# V2_rampGen.net
KiCad netlist of a schematic drawn in Altium Designer
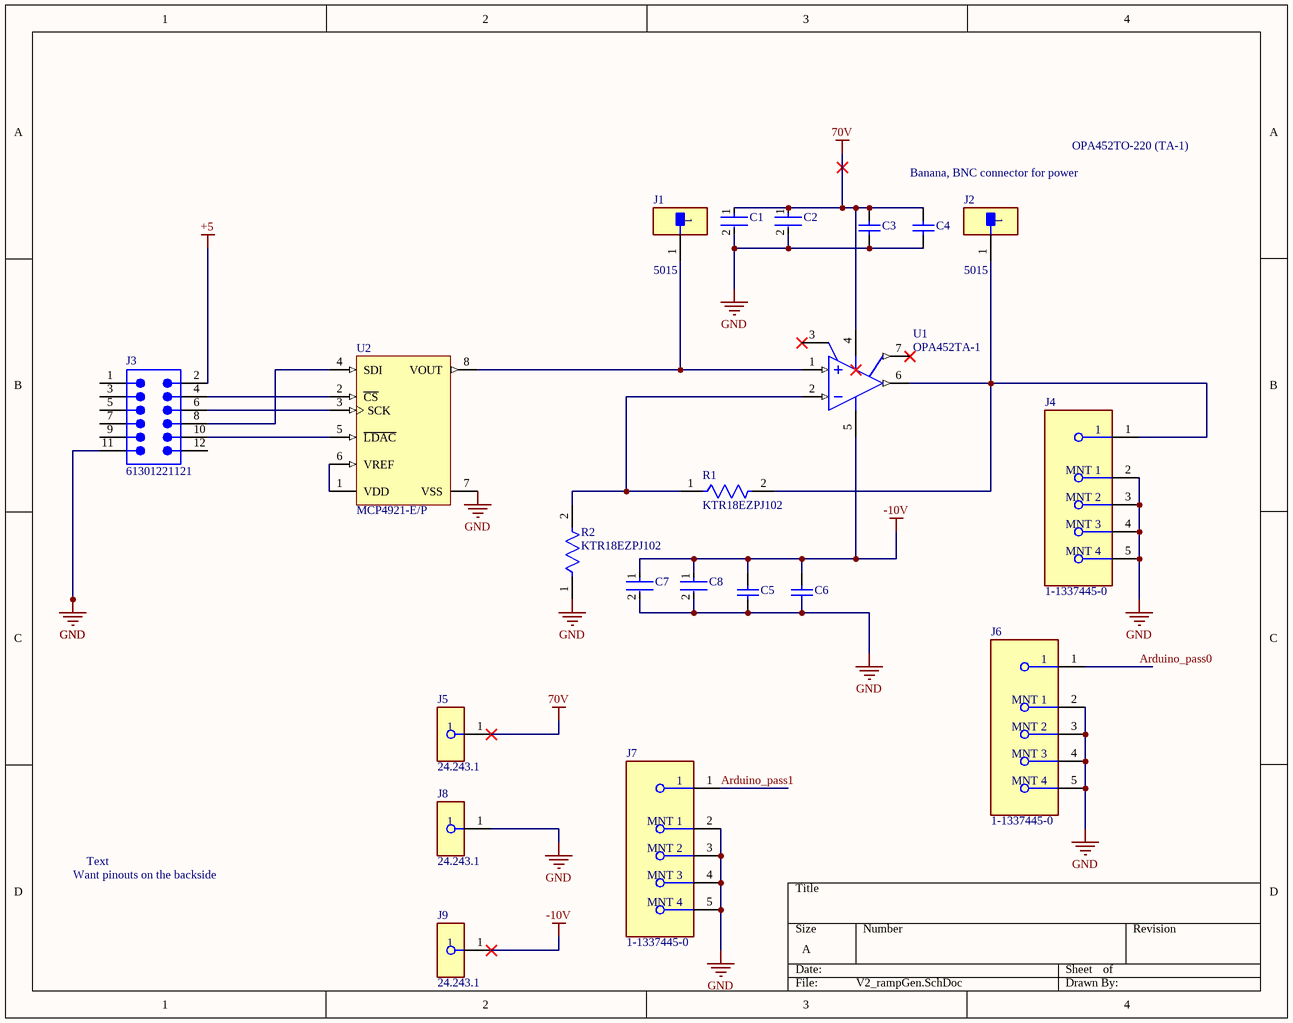
[diagram p0: V2_rampGen.SchDoc]

(export (version "E")
  (design (tool "Eeschema 10.0.6"))
  (components
    (comp (ref "C1")
      (value "C3216JB1A106M160AA")
      (footprint "FP-C3216-160-0_2-IPC_C")
      (description "Multilayer Ceramic Capacitors 10uF ±20% 10V JB SMD 1206")
      (fields (field (name "TOLERANCE") "20%"))
      (libsource (lib "Altium Content Vault") (part "11868f565c42a9108669ba33697ecf6"))
    )
    (comp (ref "C2")
      (value "C3216JB1A106M160AA")
      (footprint "FP-C3216-160-0_2-IPC_C")
      (description "Multilayer Ceramic Capacitors 10uF ±20% 10V JB SMD 1206")
      (fields (field (name "TOLERANCE") "20%"))
      (libsource (lib "Altium Content Vault") (part "11868f565c42a9108669ba33697ecf6"))
    )
    (comp (ref "C3")
      (value "CAP 100pF 100V 1206(3216)")
      (footprint "CAPC1206(3216)100_N")
      (description "CAP 100pF 100V ±1% 1206 (3216 Metric) Thickness 1mm SMD")
      (fields (field (name "TOLERANCE") "Â±1%"))
      (libsource (lib "Altium Content Vault") (part "CAP"))
    )
    (comp (ref "C4")
      (value "CAP 100pF 100V 1206(3216)")
      (footprint "CAPC1206(3216)100_N")
      (description "CAP 100pF 100V ±1% 1206 (3216 Metric) Thickness 1mm SMD")
      (fields (field (name "TOLERANCE") "Â±1%"))
      (libsource (lib "Altium Content Vault") (part "CAP"))
    )
    (comp (ref "C5")
      (value "CAP 100pF 100V 1206(3216)")
      (footprint "CAPC1206(3216)100_N")
      (description "CAP 100pF 100V ±1% 1206 (3216 Metric) Thickness 1mm SMD")
      (fields (field (name "TOLERANCE") "Â±1%"))
      (libsource (lib "Altium Content Vault") (part "CAP"))
    )
    (comp (ref "C6")
      (value "CAP 100pF 100V 1206(3216)")
      (footprint "CAPC1206(3216)100_N")
      (description "CAP 100pF 100V ±1% 1206 (3216 Metric) Thickness 1mm SMD")
      (fields (field (name "TOLERANCE") "Â±1%"))
      (libsource (lib "Altium Content Vault") (part "CAP"))
    )
    (comp (ref "C7")
      (value "C3216JB1A106M160AA")
      (footprint "FP-C3216-160-0_2-IPC_C")
      (description "Multilayer Ceramic Capacitors 10uF ±20% 10V JB SMD 1206")
      (fields (field (name "TOLERANCE") "20%"))
      (libsource (lib "Altium Content Vault") (part "11868f565c42a9108669ba33697ecf6"))
    )
    (comp (ref "C8")
      (value "C3216JB1A106M160AA")
      (footprint "FP-C3216-160-0_2-IPC_C")
      (description "Multilayer Ceramic Capacitors 10uF ±20% 10V JB SMD 1206")
      (fields (field (name "TOLERANCE") "20%"))
      (libsource (lib "Altium Content Vault") (part "11868f565c42a9108669ba33697ecf6"))
    )
    (comp (ref "J1")
      (value "5015")
      (footprint "FP-5015-MFG")
      (description "PC TEST POINT MINIATURE")
      (fields
        (field (name "MANUFACTURER") "keystone")
        (field (name "OCTOPART") "https://octopart.com/5015-keystone-3822")
      )
      (libsource (lib "Altium Content Vault") (part "dd45045ce8184df9e99e12baf3f412c"))
    )
    (comp (ref "J2")
      (value "5015")
      (footprint "FP-5015-MFG")
      (description "PC TEST POINT MINIATURE")
      (fields
        (field (name "MANUFACTURER") "keystone")
        (field (name "OCTOPART") "https://octopart.com/5015-keystone-3822")
      )
      (libsource (lib "Altium Content Vault") (part "dd45045ce8184df9e99e12baf3f412c"))
    )
    (comp (ref "J3")
      (value "61301221121")
      (footprint "61301221121")
      (libsource (lib "Altium Content Vault") (part "Header_Male_2R_12P"))
    )
    (comp (ref "J4")
      (value "1-1337445-0")
      (footprint "FP-1-1337445-0-MFG")
      (description "CONN BNC JACK STR 50 OHM PCB")
      (libsource (lib "Altium Content Vault") (part "c65b8a639cdaef1819ea20b5466f8fa"))
    )
    (comp (ref "J5")
      (value "24.243.1")
      (footprint "FP-24_243_1-MFG")
      (description "Banana Test Connector, 4mm, Socket, PCB Mount, 24 A, 60 VDC, Silver Plated Contacts, Green")
      (libsource (lib "Altium Content Vault") (part "98815daf2f2c152b0c43f5ab9800df6"))
    )
    (comp (ref "J6")
      (value "1-1337445-0")
      (footprint "FP-1-1337445-0-MFG")
      (description "CONN BNC JACK STR 50 OHM PCB")
      (libsource (lib "Altium Content Vault") (part "c65b8a639cdaef1819ea20b5466f8fa"))
    )
    (comp (ref "J7")
      (value "1-1337445-0")
      (footprint "FP-1-1337445-0-MFG")
      (description "CONN BNC JACK STR 50 OHM PCB")
      (libsource (lib "Altium Content Vault") (part "c65b8a639cdaef1819ea20b5466f8fa"))
    )
    (comp (ref "J8")
      (value "24.243.1")
      (footprint "FP-24_243_1-MFG")
      (description "Banana Test Connector, 4mm, Socket, PCB Mount, 24 A, 60 VDC, Silver Plated Contacts, Green")
      (libsource (lib "Altium Content Vault") (part "98815daf2f2c152b0c43f5ab9800df6"))
    )
    (comp (ref "J9")
      (value "24.243.1")
      (footprint "FP-24_243_1-MFG")
      (description "Banana Test Connector, 4mm, Socket, PCB Mount, 24 A, 60 VDC, Silver Plated Contacts, Green")
      (libsource (lib "Altium Content Vault") (part "98815daf2f2c152b0c43f5ab9800df6"))
    )
    (comp (ref "R1")
      (value "KTR18EZPJ102")
      (footprint "FP-KTR18-IPC_A")
      (description "Res Thick Film 1206 1kΩ 5% 0.1W ±200ppm/°C Automotive Paper T/R")
      (fields (field (name "TOLERANCE") "5%"))
      (libsource (lib "Altium Content Vault") (part "1029c3af85768c4190bb7ad29bc67b5"))
    )
    (comp (ref "R2")
      (value "KTR18EZPJ102")
      (footprint "FP-KTR18-IPC_A")
      (description "Res Thick Film 1206 1kΩ 5% 0.1W ±200ppm/°C Automotive Paper T/R")
      (fields (field (name "TOLERANCE") "5%"))
      (libsource (lib "Altium Content Vault") (part "1029c3af85768c4190bb7ad29bc67b5"))
    )
    (comp (ref "U1")
      (value "OPA452TA-1")
      (footprint "KVT0007A")
      (description "Operational Amplifier, 20 to 80 V, -40 to 125 degC, 7-pin FM (KVT7), Green (RoHS & no Sb/Br)")
      (fields (field (name "MANUFACTURER") "Texas Instruments"))
      (libsource (lib "Altium Content Vault") (part "TI-OPA452_453-7"))
    )
    (comp (ref "U2")
      (value "MCP4921-E/P")
      (footprint "PDIP300-P8")
      (description "12-Bit DAC with SPI Interface, 8-Pin PDIP, Extended Temperature")
      (libsource (lib "Altium Content Vault") (part "CON-DAC-MCP4921-8"))
    )
  )
  (nets
    (net (code "1") (name "+5") (class "Default")
      (node (ref "J3") (pin "2") (pinfunction "2_2") (pintype "passive"))
    )
    (net (code "2") (name "-10V") (class "Default")
      (node (ref "C5") (pin "2") (pinfunction "2_2") (pintype "passive"))
      (node (ref "C6") (pin "2") (pinfunction "2_2") (pintype "passive"))
      (node (ref "C7") (pin "1") (pinfunction "1_1") (pintype "passive"))
      (node (ref "C8") (pin "1") (pinfunction "1_1") (pintype "passive"))
      (node (ref "J9") (pin "1") (pinfunction "1_1") (pintype "passive"))
      (node (ref "U1") (pin "5") (pinfunction "V+_5") (pintype "power_in"))
    )
    (net (code "3") (name "/Arduino_pass0") (class "Default")
      (node (ref "J6") (pin "1") (pinfunction "1_1") (pintype "passive"))
    )
    (net (code "4") (name "/Arduino_pass1") (class "Default")
      (node (ref "J7") (pin "1") (pinfunction "1_1") (pintype "passive"))
    )
    (net (code "5") (name "70V") (class "Default")
      (node (ref "C1") (pin "1") (pinfunction "1_1") (pintype "passive"))
      (node (ref "C2") (pin "1") (pinfunction "1_1") (pintype "passive"))
      (node (ref "C3") (pin "2") (pinfunction "2_2") (pintype "passive"))
      (node (ref "C4") (pin "2") (pinfunction "2_2") (pintype "passive"))
      (node (ref "J5") (pin "1") (pinfunction "1_1") (pintype "passive"))
      (node (ref "U1") (pin "4") (pinfunction "V-_4") (pintype "power_in"))
    )
    (net (code "6") (name "GND") (class "Default")
      (node (ref "C1") (pin "2") (pinfunction "2_2") (pintype "passive"))
      (node (ref "C2") (pin "2") (pinfunction "2_2") (pintype "passive"))
      (node (ref "C3") (pin "1") (pinfunction "1_1") (pintype "passive"))
      (node (ref "C4") (pin "1") (pinfunction "1_1") (pintype "passive"))
      (node (ref "C5") (pin "1") (pinfunction "1_1") (pintype "passive"))
      (node (ref "C6") (pin "1") (pinfunction "1_1") (pintype "passive"))
      (node (ref "C7") (pin "2") (pinfunction "2_2") (pintype "passive"))
      (node (ref "C8") (pin "2") (pinfunction "2_2") (pintype "passive"))
      (node (ref "J3") (pin "11") (pinfunction "11_11") (pintype "passive"))
      (node (ref "J4") (pin "2") (pinfunction "MNT_1_2") (pintype "passive"))
      (node (ref "J4") (pin "3") (pinfunction "MNT_2_3") (pintype "passive"))
      (node (ref "J4") (pin "4") (pinfunction "MNT_3_4") (pintype "passive"))
      (node (ref "J4") (pin "5") (pinfunction "MNT_4_5") (pintype "passive"))
      (node (ref "J6") (pin "2") (pinfunction "MNT_1_2") (pintype "passive"))
      (node (ref "J6") (pin "3") (pinfunction "MNT_2_3") (pintype "passive"))
      (node (ref "J6") (pin "4") (pinfunction "MNT_3_4") (pintype "passive"))
      (node (ref "J6") (pin "5") (pinfunction "MNT_4_5") (pintype "passive"))
      (node (ref "J7") (pin "2") (pinfunction "MNT_1_2") (pintype "passive"))
      (node (ref "J7") (pin "3") (pinfunction "MNT_2_3") (pintype "passive"))
      (node (ref "J7") (pin "4") (pinfunction "MNT_3_4") (pintype "passive"))
      (node (ref "J7") (pin "5") (pinfunction "MNT_4_5") (pintype "passive"))
      (node (ref "J8") (pin "1") (pinfunction "1_1") (pintype "passive"))
      (node (ref "R2") (pin "1") (pinfunction "1_1") (pintype "passive"))
      (node (ref "U2") (pin "7") (pinfunction "VSS_7") (pintype "power_in"))
    )
    (net (code "7") (name "Net-(U1-VIN+)") (class "Default")
      (node (ref "J1") (pin "1") (pinfunction "1_1") (pintype "passive"))
      (node (ref "U1") (pin "1") (pinfunction "VIN+_1") (pintype "input"))
      (node (ref "U2") (pin "8") (pinfunction "VOUT_8") (pintype "output"))
    )
    (net (code "8") (name "Net-(U1-VIN-)") (class "Default")
      (node (ref "R1") (pin "1") (pinfunction "1_1") (pintype "passive"))
      (node (ref "R2") (pin "2") (pinfunction "2_2") (pintype "passive"))
      (node (ref "U1") (pin "2") (pinfunction "VIN-_2") (pintype "input"))
    )
    (net (code "9") (name "Net-(U1-VO)") (class "Default")
      (node (ref "J2") (pin "1") (pinfunction "1_1") (pintype "passive"))
      (node (ref "J4") (pin "1") (pinfunction "1_1") (pintype "passive"))
      (node (ref "R1") (pin "2") (pinfunction "2_2") (pintype "passive"))
      (node (ref "U1") (pin "6") (pinfunction "VO_6") (pintype "output"))
    )
    (net (code "10") (name "Net-(U2-SCK)") (class "Default")
      (node (ref "J3") (pin "6") (pinfunction "6_6") (pintype "passive"))
      (node (ref "U2") (pin "3") (pinfunction "SCK_3") (pintype "input"))
    )
    (net (code "11") (name "Net-(U2-SDI)") (class "Default")
      (node (ref "J3") (pin "8") (pinfunction "8_8") (pintype "passive"))
      (node (ref "U2") (pin "4") (pinfunction "SDI_4") (pintype "input"))
    )
    (net (code "12") (name "Net-(U2-VDD)") (class "Default")
      (node (ref "U2") (pin "1") (pinfunction "VDD_1") (pintype "power_in"))
      (node (ref "U2") (pin "6") (pinfunction "VREF_6") (pintype "input"))
    )
    (net (code "13") (name "Net-(U2-~{CS})") (class "Default")
      (node (ref "J3") (pin "4") (pinfunction "4_4") (pintype "passive"))
      (node (ref "U2") (pin "2") (pinfunction "~{CS}_2") (pintype "input"))
    )
    (net (code "14") (name "Net-(U2-~{LDAC})") (class "Default")
      (node (ref "J3") (pin "10") (pinfunction "10_10") (pintype "passive"))
      (node (ref "U2") (pin "5") (pinfunction "~{LDAC}_5") (pintype "input"))
    )
    (net (code "15") (name "unconnected-(J3-Pad1)") (class "Default")
      (node (ref "J3") (pin "1") (pinfunction "1_1") (pintype "passive"))
    )
    (net (code "16") (name "unconnected-(J3-Pad3)") (class "Default")
      (node (ref "J3") (pin "3") (pinfunction "3_3") (pintype "passive"))
    )
    (net (code "17") (name "unconnected-(J3-Pad5)") (class "Default")
      (node (ref "J3") (pin "5") (pinfunction "5_5") (pintype "passive"))
    )
    (net (code "18") (name "unconnected-(J3-Pad7)") (class "Default")
      (node (ref "J3") (pin "7") (pinfunction "7_7") (pintype "passive"))
    )
    (net (code "19") (name "unconnected-(J3-Pad9)") (class "Default")
      (node (ref "J3") (pin "9") (pinfunction "9_9") (pintype "passive"))
    )
    (net (code "20") (name "unconnected-(J3-Pad12)") (class "Default")
      (node (ref "J3") (pin "12") (pinfunction "12_12") (pintype "passive"))
    )
    (net (code "21") (name "unconnected-(U1-FLAG-Pad7)") (class "Default")
      (node (ref "U1") (pin "7") (pinfunction "FLAG_7") (pintype "output+no_connect"))
    )
    (net (code "22") (name "unconnected-(U1-NC-Pad3)") (class "Default")
      (node (ref "U1") (pin "3") (pinfunction "NC_3") (pintype "passive+no_connect"))
    )
  )
)
